# SCH_7805.net
KiCad netlist of a schematic drawn in Altium Designer
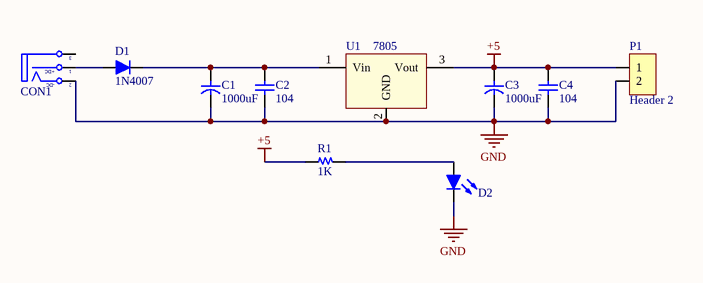
[diagram p0: SCH_7805.SchDoc]

(export (version "E")
  (design (tool "Eeschema 10.0.6"))
  (components
    (comp (ref "C1")
      (value "1000uF")
      (footprint "CYL/D.400/LS.200")
      (description "Capacitor pol")
      (libsource (lib "chipfc_libs") (part "Capacitor"))
    )
    (comp (ref "C2")
      (value "104")
      (footprint "CAP Ceramic/W300")
      (description "Capacitor non-pol")
      (libsource (lib "chipfc_libs") (part "Capacitor NP"))
    )
    (comp (ref "C3")
      (value "1000uF")
      (footprint "CYL/D.400/LS.200")
      (description "Capacitor pol")
      (libsource (lib "chipfc_libs") (part "Capacitor"))
    )
    (comp (ref "C4")
      (value "104")
      (footprint "CAP Ceramic/W300")
      (description "Capacitor non-pol")
      (libsource (lib "chipfc_libs") (part "Capacitor NP"))
    )
    (comp (ref "CON1")
      (value "CON DC PWR")
      (footprint "CONN/DC/PWR/5.0MM")
      (description "DC input connector")
      (libsource (lib "connectors") (part "CON DC PWR"))
    )
    (comp (ref "D1")
      (value "1N4007")
      (footprint "DO-35 (SOD27 )")
      (description "Default Diode")
      (libsource (lib "chipfc_libs") (part "Diode"))
    )
    (comp (ref "D2")
      (value "Led")
      (footprint "LED 5MM - RED")
      (description "Typical LED")
      (libsource (lib "chipfc_libs") (part "Led"))
    )
    (comp (ref "P1")
      (value "Header 2")
      (footprint "HDR/Terminal/2")
      (description "Header, 2-Pin")
      (libsource (lib "connectors") (part "Header 2"))
    )
    (comp (ref "R1")
      (value "1K")
      (footprint "R 1/4W/300")
      (description "Resistor")
      (libsource (lib "chipfc_libs") (part "Resistor"))
    )
    (comp (ref "U1")
      (value "7805")
      (footprint "TO-220")
      (description "LDO Fixed Voltage regulator")
      (libsource (lib "chipfc_libs") (part "78xx"))
    )
  )
  (nets
    (net (code "1") (name "+5") (class "Default")
      (node (ref "C3") (pin "1") (pinfunction "1_1") (pintype "passive"))
      (node (ref "C4") (pin "1") (pinfunction "1_1") (pintype "passive"))
      (node (ref "P1") (pin "1") (pinfunction "1_1") (pintype "passive"))
      (node (ref "R1") (pin "1") (pinfunction "1_1") (pintype "passive"))
      (node (ref "U1") (pin "3") (pinfunction "Vout_3") (pintype "passive"))
    )
    (net (code "2") (name "GND") (class "Default")
      (node (ref "C1") (pin "2") (pinfunction "2_2") (pintype "passive"))
      (node (ref "C2") (pin "2") (pinfunction "2_2") (pintype "passive"))
      (node (ref "C3") (pin "2") (pinfunction "2_2") (pintype "passive"))
      (node (ref "C4") (pin "2") (pinfunction "2_2") (pintype "passive"))
      (node (ref "CON1") (pin "2") (pinfunction "T_2") (pintype "passive"))
      (node (ref "D2") (pin "2") (pinfunction "K_2") (pintype "passive"))
      (node (ref "P1") (pin "2") (pinfunction "2_2") (pintype "passive"))
      (node (ref "U1") (pin "2") (pinfunction "GND_2") (pintype "passive"))
    )
    (net (code "3") (name "Net-(CON1-S)") (class "Default")
      (node (ref "CON1") (pin "1") (pinfunction "S_1") (pintype "power_in"))
      (node (ref "D1") (pin "1") (pinfunction "A_1") (pintype "passive"))
    )
    (net (code "4") (name "Net-(D1-K)") (class "Default")
      (node (ref "C1") (pin "1") (pinfunction "1_1") (pintype "passive"))
      (node (ref "C2") (pin "1") (pinfunction "1_1") (pintype "passive"))
      (node (ref "D1") (pin "2") (pinfunction "K_2") (pintype "passive"))
      (node (ref "U1") (pin "1") (pinfunction "Vin_1") (pintype "power_in"))
    )
    (net (code "5") (name "Net-(D2-A)") (class "Default")
      (node (ref "D2") (pin "1") (pinfunction "A_1") (pintype "passive"))
      (node (ref "R1") (pin "2") (pinfunction "2_2") (pintype "passive"))
    )
    (net (code "6") (name "unconnected-(CON1-TN-Pad3)") (class "Default")
      (node (ref "CON1") (pin "3") (pinfunction "TN_3") (pintype "passive"))
    )
  )
)
